# schematic_rxtx_adapter.net
KiCad netlist of a schematic drawn in EAGLE
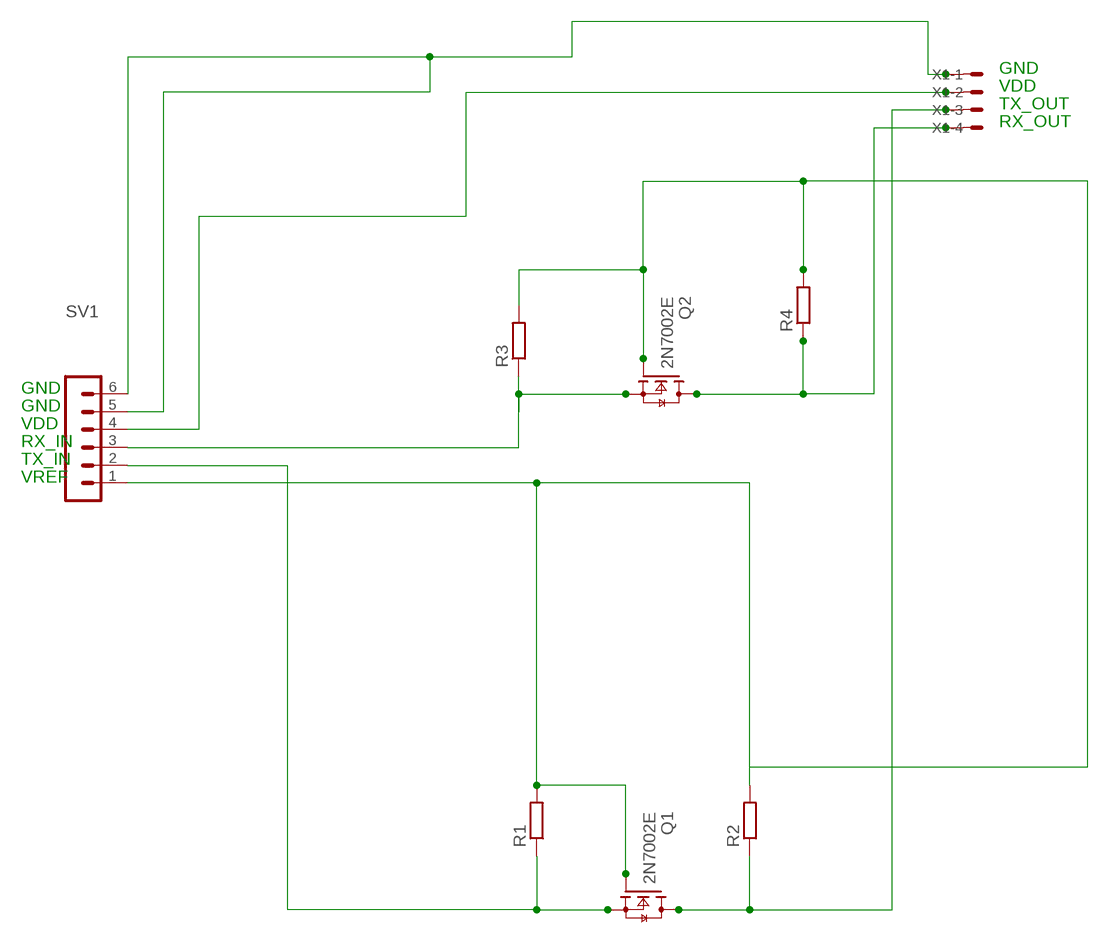
[diagram p0: schematic, sheet 1]

(export (version "E")
  (design (tool "Eeschema 10.0.6"))
  (components
    (comp (ref "Q1")
      (value "2N7002E")
      (footprint "eagle-import:SOT23")
      (libsource (lib "eagle-import") (part "2N7002E"))
    )
    (comp (ref "Q2")
      (value "2N7002E")
      (footprint "eagle-import:SOT23")
      (libsource (lib "eagle-import") (part "2N7002E"))
    )
    (comp (ref "R1")
      (value "R-EU_0207/12")
      (footprint "eagle-import:0207_12")
      (libsource (lib "eagle-import") (part "R-EU_0207/12"))
    )
    (comp (ref "R2")
      (value "R-EU_0207/12")
      (footprint "eagle-import:0207_12")
      (libsource (lib "eagle-import") (part "R-EU_0207/12"))
    )
    (comp (ref "R3")
      (value "R-EU_0207/10")
      (footprint "eagle-import:0207_10")
      (libsource (lib "eagle-import") (part "R-EU_0207/10"))
    )
    (comp (ref "R4")
      (value "R-EU_0207/10")
      (footprint "eagle-import:0207_10")
      (libsource (lib "eagle-import") (part "R-EU_0207/10"))
    )
    (comp (ref "SV1")
      (value "MA06-1")
      (footprint "eagle-import:MA06-1")
      (libsource (lib "eagle-import") (part "MA06-1"))
    )
    (comp (ref "X1")
      (value "L04P")
      (footprint "eagle-import:L04P")
      (libsource (lib "eagle-import") (part "L04P"))
    )
  )
  (nets
    (net (code "1") (name "Net-(Q1-D)") (class "Default")
      (node (ref "Q1") (pin "3") (pinfunction "D_3") (pintype "passive"))
      (node (ref "R2") (pin "1") (pinfunction "1_1") (pintype "passive"))
      (node (ref "X1") (pin "3") (pinfunction "S_3") (pintype "passive"))
    )
    (net (code "2") (name "Net-(Q1-G)") (class "Default")
      (node (ref "Q1") (pin "1") (pinfunction "G_1") (pintype "passive"))
      (node (ref "Q2") (pin "1") (pinfunction "G_1") (pintype "passive"))
      (node (ref "R1") (pin "2") (pinfunction "2_2") (pintype "passive"))
      (node (ref "R2") (pin "2") (pinfunction "2_2") (pintype "passive"))
      (node (ref "R3") (pin "2") (pinfunction "2_2") (pintype "passive"))
      (node (ref "R4") (pin "2") (pinfunction "2_2") (pintype "passive"))
      (node (ref "SV1") (pin "1") (pinfunction "1_1") (pintype "passive"))
    )
    (net (code "3") (name "Net-(Q1-S)") (class "Default")
      (node (ref "Q1") (pin "2") (pinfunction "S_2") (pintype "passive"))
      (node (ref "R1") (pin "1") (pinfunction "1_1") (pintype "passive"))
      (node (ref "SV1") (pin "2") (pinfunction "2_2") (pintype "passive"))
    )
    (net (code "4") (name "Net-(Q2-D)") (class "Default")
      (node (ref "Q2") (pin "3") (pinfunction "D_3") (pintype "passive"))
      (node (ref "R4") (pin "1") (pinfunction "1_1") (pintype "passive"))
      (node (ref "X1") (pin "4") (pinfunction "S_4") (pintype "passive"))
    )
    (net (code "5") (name "Net-(Q2-S)") (class "Default")
      (node (ref "Q2") (pin "2") (pinfunction "S_2") (pintype "passive"))
      (node (ref "R3") (pin "1") (pinfunction "1_1") (pintype "passive"))
      (node (ref "SV1") (pin "3") (pinfunction "3_3") (pintype "passive"))
    )
    (net (code "6") (name "Net-(X1A-S)") (class "Default")
      (node (ref "SV1") (pin "5") (pinfunction "5_5") (pintype "passive"))
      (node (ref "SV1") (pin "6") (pinfunction "6_6") (pintype "passive"))
      (node (ref "X1") (pin "1") (pinfunction "S_1") (pintype "passive"))
    )
    (net (code "7") (name "Net-(X1B-S)") (class "Default")
      (node (ref "SV1") (pin "4") (pinfunction "4_4") (pintype "passive"))
      (node (ref "X1") (pin "2") (pinfunction "S_2") (pintype "passive"))
    )
  )
)
